# MoleNet_v21.net
KiCad netlist of a schematic drawn in EAGLE
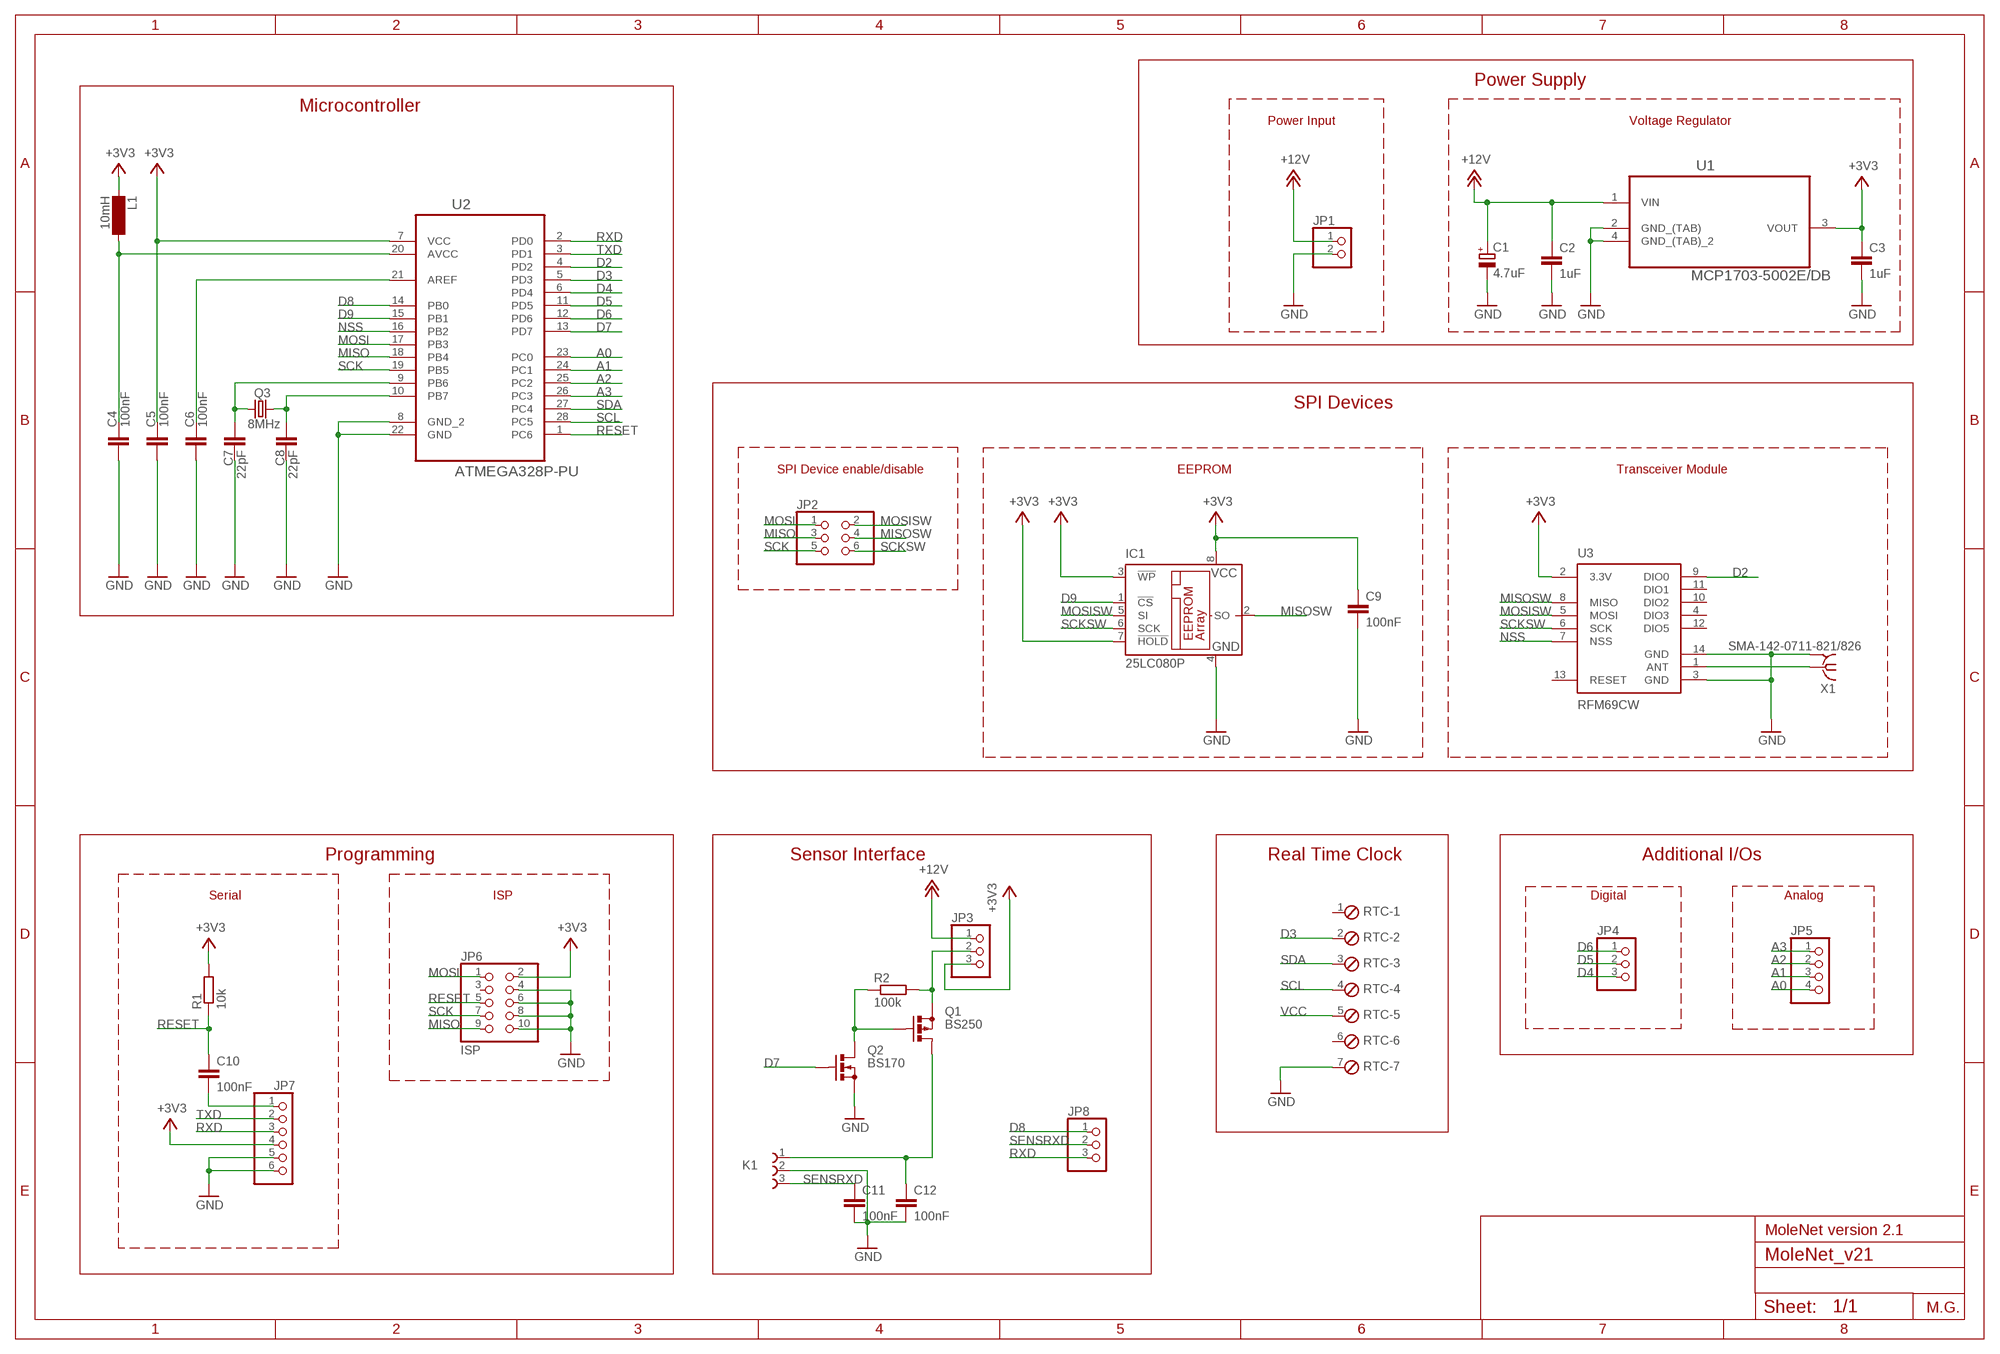
[diagram p0: schematic, sheet 1]

(export (version "E")
  (design (tool "Eeschema 10.0.6"))
  (components
    (comp (ref "C1")
      (value "4.7uF")
      (footprint "eagle-import:E2,5-6")
      (libsource (lib "eagle-import") (part "CPOL-EUE2.5-6"))
    )
    (comp (ref "C2")
      (value "1uF")
      (footprint "eagle-import:C025-025X050")
      (libsource (lib "eagle-import") (part "C-EU025-025X050"))
    )
    (comp (ref "C3")
      (value "1uF")
      (footprint "eagle-import:C025-025X050")
      (libsource (lib "eagle-import") (part "C-EU025-025X050"))
    )
    (comp (ref "C4")
      (value "100nF")
      (footprint "eagle-import:C025-025X050")
      (libsource (lib "eagle-import") (part "C-EU025-025X050"))
    )
    (comp (ref "C5")
      (value "100nF")
      (footprint "eagle-import:C025-025X050")
      (libsource (lib "eagle-import") (part "C-EU025-025X050"))
    )
    (comp (ref "C6")
      (value "100nF")
      (footprint "eagle-import:C025-025X050")
      (libsource (lib "eagle-import") (part "C-EU025-025X050"))
    )
    (comp (ref "C7")
      (value "22pF")
      (footprint "eagle-import:C025-025X050")
      (libsource (lib "eagle-import") (part "C-EU025-025X050"))
    )
    (comp (ref "C8")
      (value "22pF")
      (footprint "eagle-import:C025-025X050")
      (libsource (lib "eagle-import") (part "C-EU025-025X050"))
    )
    (comp (ref "C9")
      (value "100nF")
      (footprint "eagle-import:C025-025X050")
      (libsource (lib "eagle-import") (part "C-EU025-025X050"))
    )
    (comp (ref "C10")
      (value "100nF")
      (footprint "eagle-import:C025-025X050")
      (libsource (lib "eagle-import") (part "C-EU025-025X050"))
    )
    (comp (ref "C11")
      (value "100nF")
      (footprint "eagle-import:C025-025X050")
      (libsource (lib "eagle-import") (part "C-EU025-025X050"))
    )
    (comp (ref "C12")
      (value "100nF")
      (footprint "eagle-import:C025-025X050")
      (libsource (lib "eagle-import") (part "C-EU025-025X050"))
    )
    (comp (ref "IC1")
      (value "25LC080P")
      (footprint "eagle-import:DIL8")
      (fields (field (name "MF") "MICROCHIP") (field (name "MPN") "25LC080/P"))
      (libsource (lib "eagle-import") (part "25PLC080"))
    )
    (comp (ref "JP1")
      (value "PINHD-1X2")
      (footprint "eagle-import:1X02")
      (libsource (lib "eagle-import") (part "PINHD-1X2"))
    )
    (comp (ref "JP2")
      (value "PINHD-2X3")
      (footprint "eagle-import:2X03")
      (libsource (lib "eagle-import") (part "PINHD-2X3"))
    )
    (comp (ref "JP3")
      (value "PINHD-1X3")
      (footprint "eagle-import:1X03")
      (libsource (lib "eagle-import") (part "PINHD-1X3"))
    )
    (comp (ref "JP4")
      (value "PINHD-1X3")
      (footprint "eagle-import:1X03")
      (libsource (lib "eagle-import") (part "PINHD-1X3"))
    )
    (comp (ref "JP5")
      (value "PINHD-1X4")
      (footprint "eagle-import:1X04")
      (libsource (lib "eagle-import") (part "PINHD-1X4"))
    )
    (comp (ref "JP6")
      (value "ISP")
      (footprint "eagle-import:2X05")
      (libsource (lib "eagle-import") (part "PINHD-2X5"))
    )
    (comp (ref "JP7")
      (value "PINHD-1X6")
      (footprint "eagle-import:1X06")
      (libsource (lib "eagle-import") (part "PINHD-1X6"))
    )
    (comp (ref "JP8")
      (value "PINHD-1X3")
      (footprint "eagle-import:1X03")
      (libsource (lib "eagle-import") (part "PINHD-1X3"))
    )
    (comp (ref "K1")
      (value "691241710003")
      (footprint "eagle-import:691241710003")
      (libsource (lib "eagle-import") (part "691241710003"))
    )
    (comp (ref "L1")
      (value "10mH")
      (footprint "eagle-import:BS11")
      (libsource (lib "eagle-import") (part "BS11"))
    )
    (comp (ref "Q1")
      (value "BS250")
      (footprint "eagle-import:SOT54E")
      (libsource (lib "eagle-import") (part "BS250"))
    )
    (comp (ref "Q2")
      (value "BS170")
      (footprint "eagle-import:SOT54E")
      (libsource (lib "eagle-import") (part "BS170"))
    )
    (comp (ref "Q3")
      (value "8MHz")
      (footprint "eagle-import:HC18U-V")
      (libsource (lib "eagle-import") (part "CRYSTALHC18U-V"))
    )
    (comp (ref "R1")
      (value "10k")
      (footprint "eagle-import:0207_10")
      (libsource (lib "eagle-import") (part "R-EU_0207/10"))
    )
    (comp (ref "R2")
      (value "100k")
      (footprint "eagle-import:0207_10")
      (libsource (lib "eagle-import") (part "R-EU_0207/10"))
    )
    (comp (ref "RTC")
      (value "MPT7")
      (footprint "eagle-import:7POL254")
      (libsource (lib "eagle-import") (part "MPT7"))
    )
    (comp (ref "U1")
      (value "MCP1703-5002E/DB")
      (footprint "eagle-import:SOT230P700X180-4N")
      (libsource (lib "eagle-import") (part "MCP1703-5002E/DB"))
    )
    (comp (ref "U2")
      (value "ATMEGA328P-PU")
      (footprint "eagle-import:DIP254P762X457-28")
      (libsource (lib "eagle-import") (part "ATMEGA328P-PU"))
    )
    (comp (ref "U3")
      (value "RFM69CW")
      (footprint "eagle-import:RFM69CW-XXXS2")
      (libsource (lib "eagle-import") (part "RFM69CW"))
    )
    (comp (ref "X1")
      (value "SMA-142-0711-821/826")
      (footprint "eagle-import:J502-ND-142-0711-821_826")
      (fields (field (name "MF") "JOHNSON COMPONENTS") (field (name "MPN") "142-0711-821"))
      (libsource (lib "eagle-import") (part "SMA-142-0711-821/826"))
    )
  )
  (nets
    (net (code "1") (name "+3V3") (class "Default")
      (node (ref "C3") (pin "1") (pinfunction "1_1") (pintype "passive"))
      (node (ref "C5") (pin "1") (pinfunction "1_1") (pintype "passive"))
      (node (ref "C9") (pin "1") (pinfunction "1_1") (pintype "passive"))
      (node (ref "IC1") (pin "3") (pinfunction "~{WP}_3") (pintype "input"))
      (node (ref "IC1") (pin "7") (pinfunction "~{HOLD}_7") (pintype "input"))
      (node (ref "IC1") (pin "8") (pinfunction "VCC_8") (pintype "power_in"))
      (node (ref "JP3") (pin "3") (pinfunction "3_3") (pintype "passive"))
      (node (ref "JP6") (pin "2") (pinfunction "2_2") (pintype "passive"))
      (node (ref "JP7") (pin "4") (pinfunction "4_4") (pintype "passive"))
      (node (ref "L1") (pin "1") (pinfunction "1_1") (pintype "passive"))
      (node (ref "R1") (pin "2") (pinfunction "2_2") (pintype "passive"))
      (node (ref "RTC") (pin "5") (pinfunction "1_5") (pintype "passive"))
      (node (ref "U1") (pin "3") (pinfunction "VOUT_3") (pintype "output"))
      (node (ref "U2") (pin "7") (pinfunction "VCC_7") (pintype "power_in"))
      (node (ref "U3") (pin "2") (pinfunction "3.3V_2") (pintype "power_in"))
    )
    (net (code "2") (name "+12V") (class "Default")
      (node (ref "C1") (pin "+") (pinfunction "+_+") (pintype "passive"))
      (node (ref "C2") (pin "1") (pinfunction "1_1") (pintype "passive"))
      (node (ref "JP1") (pin "1") (pinfunction "1_1") (pintype "passive"))
      (node (ref "JP3") (pin "1") (pinfunction "1_1") (pintype "passive"))
      (node (ref "U1") (pin "1") (pinfunction "VIN_1") (pintype "input"))
    )
    (net (code "3") (name "/A0") (class "Default")
      (node (ref "JP5") (pin "4") (pinfunction "4_4") (pintype "passive"))
      (node (ref "U2") (pin "23") (pinfunction "PC0_23") (pintype "bidirectional"))
    )
    (net (code "4") (name "/A1") (class "Default")
      (node (ref "JP5") (pin "3") (pinfunction "3_3") (pintype "passive"))
      (node (ref "U2") (pin "24") (pinfunction "PC1_24") (pintype "bidirectional"))
    )
    (net (code "5") (name "/A2") (class "Default")
      (node (ref "JP5") (pin "2") (pinfunction "2_2") (pintype "passive"))
      (node (ref "U2") (pin "25") (pinfunction "PC2_25") (pintype "bidirectional"))
    )
    (net (code "6") (name "/A3") (class "Default")
      (node (ref "JP5") (pin "1") (pinfunction "1_1") (pintype "passive"))
      (node (ref "U2") (pin "26") (pinfunction "PC3_26") (pintype "bidirectional"))
    )
    (net (code "7") (name "/D2") (class "Default")
      (node (ref "U2") (pin "4") (pinfunction "PD2_4") (pintype "bidirectional"))
      (node (ref "U3") (pin "9") (pinfunction "DIO0_9") (pintype "bidirectional"))
    )
    (net (code "8") (name "/D3") (class "Default")
      (node (ref "RTC") (pin "2") (pinfunction "1_2") (pintype "passive"))
      (node (ref "U2") (pin "5") (pinfunction "PD3_5") (pintype "bidirectional"))
    )
    (net (code "9") (name "/D4") (class "Default")
      (node (ref "JP4") (pin "3") (pinfunction "3_3") (pintype "passive"))
      (node (ref "U2") (pin "6") (pinfunction "PD4_6") (pintype "bidirectional"))
    )
    (net (code "10") (name "/D5") (class "Default")
      (node (ref "JP4") (pin "2") (pinfunction "2_2") (pintype "passive"))
      (node (ref "U2") (pin "11") (pinfunction "PD5_11") (pintype "bidirectional"))
    )
    (net (code "11") (name "/D6") (class "Default")
      (node (ref "JP4") (pin "1") (pinfunction "1_1") (pintype "passive"))
      (node (ref "U2") (pin "12") (pinfunction "PD6_12") (pintype "bidirectional"))
    )
    (net (code "12") (name "/D7") (class "Default")
      (node (ref "Q2") (pin "G") (pinfunction "G_G") (pintype "passive"))
      (node (ref "U2") (pin "13") (pinfunction "PD7_13") (pintype "bidirectional"))
    )
    (net (code "13") (name "/D8") (class "Default")
      (node (ref "JP8") (pin "1") (pinfunction "1_1") (pintype "passive"))
      (node (ref "U2") (pin "14") (pinfunction "PB0_14") (pintype "bidirectional"))
    )
    (net (code "14") (name "/D9") (class "Default")
      (node (ref "IC1") (pin "1") (pinfunction "~{CS}_1") (pintype "input"))
      (node (ref "U2") (pin "15") (pinfunction "PB1_15") (pintype "bidirectional"))
    )
    (net (code "15") (name "/MISO") (class "Default")
      (node (ref "JP2") (pin "3") (pinfunction "3_3") (pintype "passive"))
      (node (ref "JP6") (pin "9") (pinfunction "9_9") (pintype "passive"))
      (node (ref "U2") (pin "18") (pinfunction "PB4_18") (pintype "bidirectional"))
    )
    (net (code "16") (name "/MISOSW") (class "Default")
      (node (ref "IC1") (pin "2") (pinfunction "SO_2") (pintype "bidirectional"))
      (node (ref "JP2") (pin "4") (pinfunction "4_4") (pintype "passive"))
      (node (ref "U3") (pin "8") (pinfunction "MISO_8") (pintype "bidirectional"))
    )
    (net (code "17") (name "/MOSI") (class "Default")
      (node (ref "JP2") (pin "1") (pinfunction "1_1") (pintype "passive"))
      (node (ref "JP6") (pin "1") (pinfunction "1_1") (pintype "passive"))
      (node (ref "U2") (pin "17") (pinfunction "PB3_17") (pintype "bidirectional"))
    )
    (net (code "18") (name "/MOSISW") (class "Default")
      (node (ref "IC1") (pin "5") (pinfunction "SI_5") (pintype "input"))
      (node (ref "JP2") (pin "2") (pinfunction "2_2") (pintype "passive"))
      (node (ref "U3") (pin "5") (pinfunction "MOSI_5") (pintype "input"))
    )
    (net (code "19") (name "/NSS") (class "Default")
      (node (ref "U2") (pin "16") (pinfunction "PB2_16") (pintype "bidirectional"))
      (node (ref "U3") (pin "7") (pinfunction "NSS_7") (pintype "input"))
    )
    (net (code "20") (name "/RESET") (class "Default")
      (node (ref "C10") (pin "1") (pinfunction "1_1") (pintype "passive"))
      (node (ref "JP6") (pin "5") (pinfunction "5_5") (pintype "passive"))
      (node (ref "R1") (pin "1") (pinfunction "1_1") (pintype "passive"))
      (node (ref "U2") (pin "1") (pinfunction "PC6_1") (pintype "bidirectional"))
    )
    (net (code "21") (name "/RXD") (class "Default")
      (node (ref "JP7") (pin "3") (pinfunction "3_3") (pintype "passive"))
      (node (ref "JP8") (pin "3") (pinfunction "3_3") (pintype "passive"))
      (node (ref "U2") (pin "2") (pinfunction "PD0_2") (pintype "bidirectional"))
    )
    (net (code "22") (name "/SCK") (class "Default")
      (node (ref "JP2") (pin "5") (pinfunction "5_5") (pintype "passive"))
      (node (ref "JP6") (pin "7") (pinfunction "7_7") (pintype "passive"))
      (node (ref "U2") (pin "19") (pinfunction "PB5_19") (pintype "bidirectional"))
    )
    (net (code "23") (name "/SCKSW") (class "Default")
      (node (ref "IC1") (pin "6") (pinfunction "SCK_6") (pintype "input"))
      (node (ref "JP2") (pin "6") (pinfunction "6_6") (pintype "passive"))
      (node (ref "U3") (pin "6") (pinfunction "SCK_6") (pintype "input"))
    )
    (net (code "24") (name "/SCL") (class "Default")
      (node (ref "RTC") (pin "4") (pinfunction "1_4") (pintype "passive"))
      (node (ref "U2") (pin "28") (pinfunction "PC5_28") (pintype "bidirectional"))
    )
    (net (code "25") (name "/SDA") (class "Default")
      (node (ref "RTC") (pin "3") (pinfunction "1_3") (pintype "passive"))
      (node (ref "U2") (pin "27") (pinfunction "PC4_27") (pintype "bidirectional"))
    )
    (net (code "26") (name "/SENSRXD") (class "Default")
      (node (ref "C11") (pin "1") (pinfunction "1_1") (pintype "passive"))
      (node (ref "JP8") (pin "2") (pinfunction "2_2") (pintype "passive"))
      (node (ref "K1") (pin "3") (pinfunction "3_3") (pintype "passive"))
    )
    (net (code "27") (name "/TXD") (class "Default")
      (node (ref "JP7") (pin "2") (pinfunction "2_2") (pintype "passive"))
      (node (ref "U2") (pin "3") (pinfunction "PD1_3") (pintype "bidirectional"))
    )
    (net (code "28") (name "GND") (class "Default")
      (node (ref "C1") (pin "-") (pinfunction "-_-") (pintype "passive"))
      (node (ref "C11") (pin "2") (pinfunction "2_2") (pintype "passive"))
      (node (ref "C12") (pin "2") (pinfunction "2_2") (pintype "passive"))
      (node (ref "C2") (pin "2") (pinfunction "2_2") (pintype "passive"))
      (node (ref "C3") (pin "2") (pinfunction "2_2") (pintype "passive"))
      (node (ref "C4") (pin "2") (pinfunction "2_2") (pintype "passive"))
      (node (ref "C5") (pin "2") (pinfunction "2_2") (pintype "passive"))
      (node (ref "C6") (pin "2") (pinfunction "2_2") (pintype "passive"))
      (node (ref "C7") (pin "2") (pinfunction "2_2") (pintype "passive"))
      (node (ref "C8") (pin "2") (pinfunction "2_2") (pintype "passive"))
      (node (ref "C9") (pin "2") (pinfunction "2_2") (pintype "passive"))
      (node (ref "IC1") (pin "4") (pinfunction "GND_4") (pintype "power_in"))
      (node (ref "JP1") (pin "2") (pinfunction "2_2") (pintype "passive"))
      (node (ref "JP6") (pin "10") (pinfunction "10_10") (pintype "passive"))
      (node (ref "JP6") (pin "4") (pinfunction "4_4") (pintype "passive"))
      (node (ref "JP6") (pin "6") (pinfunction "6_6") (pintype "passive"))
      (node (ref "JP6") (pin "8") (pinfunction "8_8") (pintype "passive"))
      (node (ref "JP7") (pin "5") (pinfunction "5_5") (pintype "passive"))
      (node (ref "JP7") (pin "6") (pinfunction "6_6") (pintype "passive"))
      (node (ref "K1") (pin "2") (pinfunction "2_2") (pintype "passive"))
      (node (ref "Q2") (pin "S") (pinfunction "S_S") (pintype "passive"))
      (node (ref "RTC") (pin "7") (pinfunction "1_7") (pintype "passive"))
      (node (ref "U1") (pin "2") (pinfunction "GND_(TAB)_2") (pintype "passive"))
      (node (ref "U1") (pin "4") (pinfunction "GND_(TAB)_2_4") (pintype "passive"))
      (node (ref "U2") (pin "22") (pinfunction "GND_22") (pintype "passive"))
      (node (ref "U2") (pin "8") (pinfunction "GND_2_8") (pintype "passive"))
      (node (ref "U3") (pin "14") (pinfunction "GND_14") (pintype "power_in"))
      (node (ref "U3") (pin "3") (pinfunction "GND_3") (pintype "power_in"))
      (node (ref "X1") (pin "G@1") (pinfunction "2_G@1") (pintype "passive"))
      (node (ref "X1") (pin "G@2") (pinfunction "2_G@2") (pintype "passive"))
      (node (ref "X1") (pin "G@3") (pinfunction "2_G@3") (pintype "passive"))
      (node (ref "X1") (pin "G@4") (pinfunction "2_G@4") (pintype "passive"))
    )
    (net (code "29") (name "Net-(C10-Pad2)") (class "Default")
      (node (ref "C10") (pin "2") (pinfunction "2_2") (pintype "passive"))
      (node (ref "JP7") (pin "1") (pinfunction "1_1") (pintype "passive"))
    )
    (net (code "30") (name "Net-(C12-Pad1)") (class "Default")
      (node (ref "C12") (pin "1") (pinfunction "1_1") (pintype "passive"))
      (node (ref "K1") (pin "1") (pinfunction "1_1") (pintype "passive"))
      (node (ref "Q1") (pin "D") (pinfunction "D_D") (pintype "passive"))
    )
    (net (code "31") (name "Net-(JP3-Pad2)") (class "Default")
      (node (ref "JP3") (pin "2") (pinfunction "2_2") (pintype "passive"))
      (node (ref "Q1") (pin "S") (pinfunction "S_S") (pintype "passive"))
      (node (ref "R2") (pin "2") (pinfunction "2_2") (pintype "passive"))
    )
    (net (code "32") (name "Net-(Q1-PadG)") (class "Default")
      (node (ref "Q1") (pin "G") (pinfunction "G_G") (pintype "passive"))
      (node (ref "Q2") (pin "D") (pinfunction "D_D") (pintype "passive"))
      (node (ref "R2") (pin "1") (pinfunction "1_1") (pintype "passive"))
    )
    (net (code "33") (name "Net-(U2-AREF)") (class "Default")
      (node (ref "C6") (pin "1") (pinfunction "1_1") (pintype "passive"))
      (node (ref "U2") (pin "21") (pinfunction "AREF_21") (pintype "input"))
    )
    (net (code "34") (name "Net-(U2-AVCC)") (class "Default")
      (node (ref "C4") (pin "1") (pinfunction "1_1") (pintype "passive"))
      (node (ref "L1") (pin "2") (pinfunction "2_2") (pintype "passive"))
      (node (ref "U2") (pin "20") (pinfunction "AVCC_20") (pintype "power_in"))
    )
    (net (code "35") (name "Net-(U2-PB6)") (class "Default")
      (node (ref "C7") (pin "1") (pinfunction "1_1") (pintype "passive"))
      (node (ref "Q3") (pin "1") (pinfunction "1_1") (pintype "passive"))
      (node (ref "U2") (pin "9") (pinfunction "PB6_9") (pintype "bidirectional"))
    )
    (net (code "36") (name "Net-(U2-PB7)") (class "Default")
      (node (ref "C8") (pin "1") (pinfunction "1_1") (pintype "passive"))
      (node (ref "Q3") (pin "2") (pinfunction "2_2") (pintype "passive"))
      (node (ref "U2") (pin "10") (pinfunction "PB7_10") (pintype "bidirectional"))
    )
    (net (code "37") (name "Net-(U3-ANT)") (class "Default")
      (node (ref "U3") (pin "1") (pinfunction "ANT_1") (pintype "passive"))
      (node (ref "X1") (pin "1") (pinfunction "1_1") (pintype "passive"))
    )
    (net (code "38") (name "unconnected-(JP6-Pad3)") (class "Default")
      (node (ref "JP6") (pin "3") (pinfunction "3_3") (pintype "passive"))
    )
    (net (code "39") (name "unconnected-(RTC-Pad1)") (class "Default")
      (node (ref "RTC") (pin "1") (pinfunction "1_1") (pintype "passive"))
    )
    (net (code "40") (name "unconnected-(RTCF-1-Pad6)") (class "Default")
      (node (ref "RTC") (pin "6") (pinfunction "1_6") (pintype "passive"))
    )
    (net (code "41") (name "unconnected-(U3-DIO1-Pad11)") (class "Default")
      (node (ref "U3") (pin "11") (pinfunction "DIO1_11") (pintype "bidirectional"))
    )
    (net (code "42") (name "unconnected-(U3-DIO2-Pad10)") (class "Default")
      (node (ref "U3") (pin "10") (pinfunction "DIO2_10") (pintype "bidirectional"))
    )
    (net (code "43") (name "unconnected-(U3-DIO3-Pad4)") (class "Default")
      (node (ref "U3") (pin "4") (pinfunction "DIO3_4") (pintype "bidirectional"))
    )
    (net (code "44") (name "unconnected-(U3-DIO5-Pad12)") (class "Default")
      (node (ref "U3") (pin "12") (pinfunction "DIO5_12") (pintype "bidirectional"))
    )
    (net (code "45") (name "unconnected-(U3-RESET-Pad13)") (class "Default")
      (node (ref "U3") (pin "13") (pinfunction "RESET_13") (pintype "input"))
    )
  )
)
